# 5-Brake_Temp_Sensors.net
KiCad netlist of a schematic drawn in Altium Designer
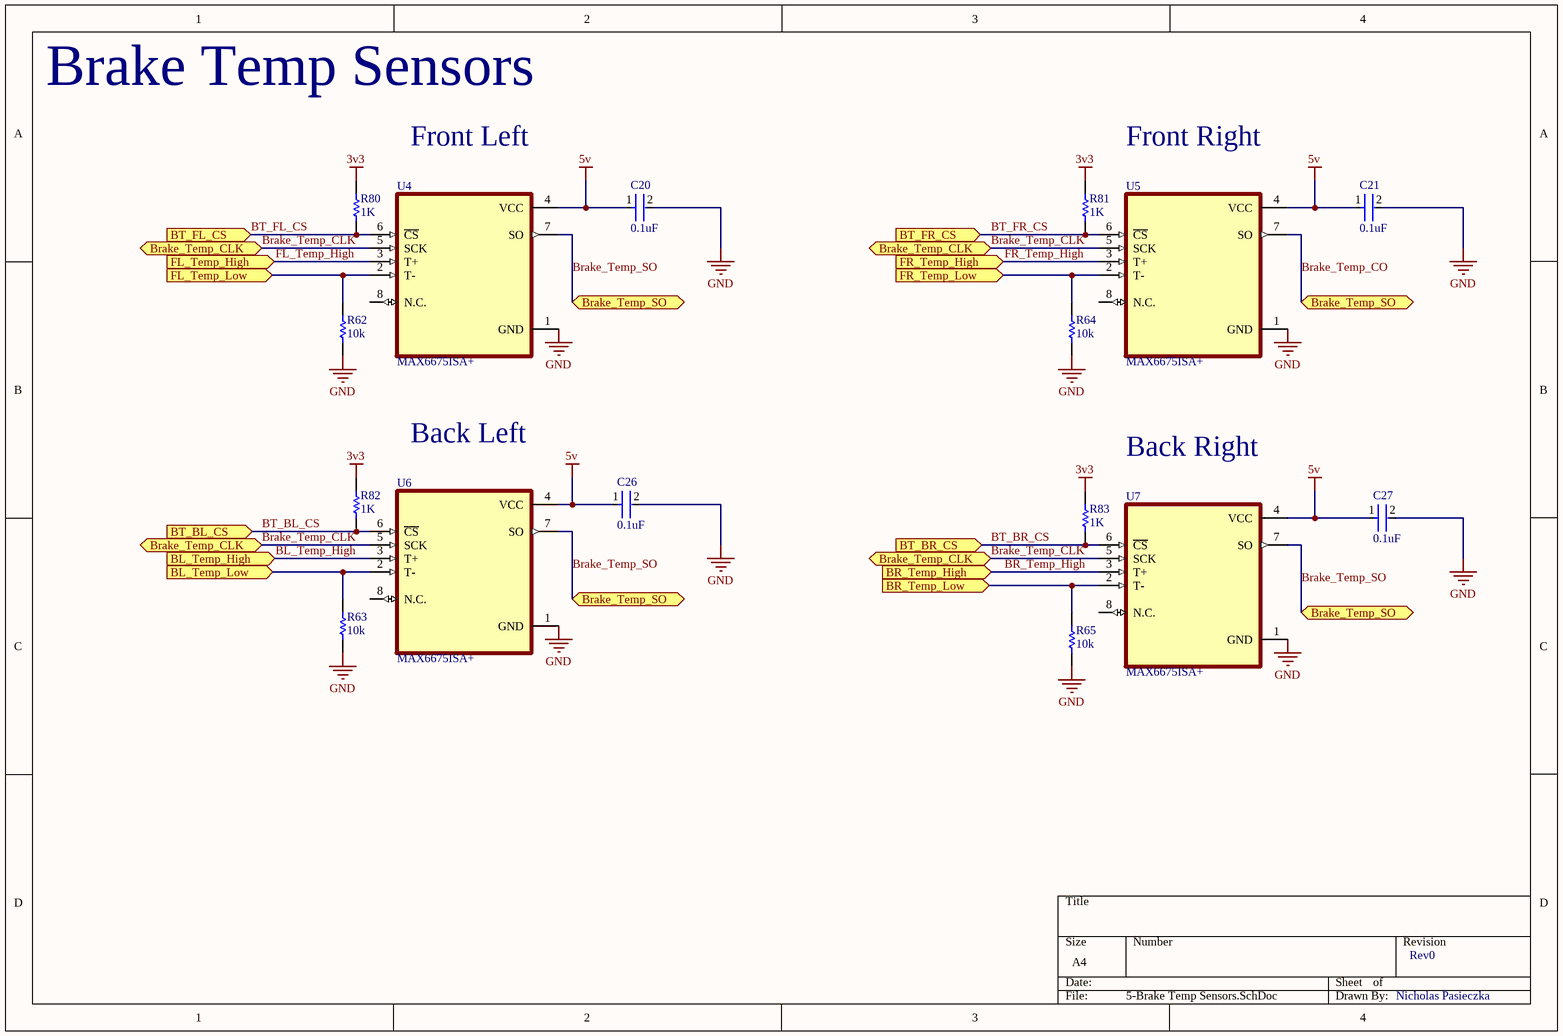
[diagram p0: 5-Brake Temp Sensors.SchDoc]

(export (version "E")
  (design (tool "Eeschema 10.0.6"))
  (components
    (comp (ref "C20")
      (value "0.1uF")
      (footprint "FP-CL17-IPC_C")
      (description "Cap Ceramic 100nF 10V X7R ±10% SMD 0402 +125°C Paper T/R")
      (fields (field (name "TOLERANCE") "10%"))
      (libsource (lib "Altium Content Vault") (part "b4654b650e69147ec39a6b967a45e02"))
    )
    (comp (ref "C21")
      (value "0.1uF")
      (footprint "FP-CL17-IPC_C")
      (description "Cap Ceramic 100nF 10V X7R ±10% SMD 0402 +125°C Paper T/R")
      (fields (field (name "TOLERANCE") "10%"))
      (libsource (lib "Altium Content Vault") (part "b4654b650e69147ec39a6b967a45e02"))
    )
    (comp (ref "C26")
      (value "0.1uF")
      (footprint "FP-CL17-IPC_C")
      (description "Cap Ceramic 100nF 10V X7R ±10% SMD 0402 +125°C Paper T/R")
      (fields (field (name "TOLERANCE") "10%"))
      (libsource (lib "Altium Content Vault") (part "b4654b650e69147ec39a6b967a45e02"))
    )
    (comp (ref "C27")
      (value "0.1uF")
      (footprint "FP-CL17-IPC_C")
      (description "Cap Ceramic 100nF 10V X7R ±10% SMD 0402 +125°C Paper T/R")
      (fields (field (name "TOLERANCE") "10%"))
      (libsource (lib "Altium Content Vault") (part "b4654b650e69147ec39a6b967a45e02"))
    )
    (comp (ref "R62")
      (value "10k")
      (footprint "1608[0603]")
      (description "Resistor")
      (fields
        (field (name "MANUFACTURER") "Yageo")
        (field (name "MANUFACTURER PART NUMBER") "RC0603JR-0710KL")
      )
      (libsource (lib "Miscellaneous Devices") (part "Res1"))
    )
    (comp (ref "R63")
      (value "10k")
      (footprint "1608[0603]")
      (description "Resistor")
      (fields
        (field (name "MANUFACTURER") "Yageo")
        (field (name "MANUFACTURER PART NUMBER") "RC0603JR-0710KL")
      )
      (libsource (lib "Miscellaneous Devices") (part "Res1"))
    )
    (comp (ref "R64")
      (value "10k")
      (footprint "1608[0603]")
      (description "Resistor")
      (fields
        (field (name "MANUFACTURER") "Yageo")
        (field (name "MANUFACTURER PART NUMBER") "RC0603JR-0710KL")
      )
      (libsource (lib "Miscellaneous Devices") (part "Res1"))
    )
    (comp (ref "R65")
      (value "10k")
      (footprint "1608[0603]")
      (description "Resistor")
      (fields
        (field (name "MANUFACTURER") "Yageo")
        (field (name "MANUFACTURER PART NUMBER") "RC0603JR-0710KL")
      )
      (libsource (lib "Miscellaneous Devices") (part "Res1"))
    )
    (comp (ref "R80")
      (value "1K")
      (footprint "1608[0603]")
      (description "Resistor")
      (fields (field (name "Comment") "Res1") (field (name "PUBLISHER") "Altium Limited"))
      (libsource (lib "Miscellaneous Devices") (part "Res1"))
    )
    (comp (ref "R81")
      (value "1K")
      (footprint "1608[0603]")
      (description "Resistor")
      (fields (field (name "Comment") "Res1") (field (name "PUBLISHER") "Altium Limited"))
      (libsource (lib "Miscellaneous Devices") (part "Res1"))
    )
    (comp (ref "R82")
      (value "1K")
      (footprint "1608[0603]")
      (description "Resistor")
      (fields (field (name "Comment") "Res1") (field (name "PUBLISHER") "Altium Limited"))
      (libsource (lib "Miscellaneous Devices") (part "Res1"))
    )
    (comp (ref "R83")
      (value "1K")
      (footprint "1608[0603]")
      (description "Resistor")
      (fields (field (name "Comment") "Res1") (field (name "PUBLISHER") "Altium Limited"))
      (libsource (lib "Miscellaneous Devices") (part "Res1"))
    )
    (comp (ref "U4")
      (value "MAX6675ISA+")
      (footprint "SOIC127P600X175-8N")
      (description "IC THERMOCOUP TO DGTL 8-SOIC")
      (fields (field (name "MF") "Maxim Integrated"))
      (libsource (lib "MAX6675ISA_") (part "MAX6675ISA+"))
    )
    (comp (ref "U5")
      (value "MAX6675ISA+")
      (footprint "SOIC127P600X175-8N")
      (description "IC THERMOCOUP TO DGTL 8-SOIC")
      (fields (field (name "MF") "Maxim Integrated"))
      (libsource (lib "MAX6675ISA_") (part "MAX6675ISA+"))
    )
    (comp (ref "U6")
      (value "MAX6675ISA+")
      (footprint "SOIC127P600X175-8N")
      (description "IC THERMOCOUP TO DGTL 8-SOIC")
      (fields (field (name "MF") "Maxim Integrated"))
      (libsource (lib "MAX6675ISA_") (part "MAX6675ISA+"))
    )
    (comp (ref "U7")
      (value "MAX6675ISA+")
      (footprint "SOIC127P600X175-8N")
      (description "IC THERMOCOUP TO DGTL 8-SOIC")
      (fields (field (name "MF") "Maxim Integrated"))
      (libsource (lib "MAX6675ISA_") (part "MAX6675ISA+"))
    )
  )
  (nets
    (net (code "1") (name "/BL_Temp_High") (class "Default")
      (node (ref "U6") (pin "3") (pinfunction "T+_3") (pintype "input"))
    )
    (net (code "2") (name "/BL_Temp_Low") (class "Default")
      (node (ref "R63") (pin "2") (pinfunction "2_2") (pintype "passive"))
      (node (ref "U6") (pin "2") (pinfunction "T-_2") (pintype "input"))
    )
    (net (code "3") (name "/BR_Temp_High") (class "Default")
      (node (ref "U7") (pin "3") (pinfunction "T+_3") (pintype "input"))
    )
    (net (code "4") (name "/BR_Temp_Low") (class "Default")
      (node (ref "R65") (pin "2") (pinfunction "2_2") (pintype "passive"))
      (node (ref "U7") (pin "2") (pinfunction "T-_2") (pintype "input"))
    )
    (net (code "5") (name "/BT_BL_CS") (class "Default")
      (node (ref "R82") (pin "1") (pinfunction "1_1") (pintype "passive"))
      (node (ref "U6") (pin "6") (pinfunction "~{CS}_6") (pintype "input"))
    )
    (net (code "6") (name "/BT_BR_CS") (class "Default")
      (node (ref "R83") (pin "1") (pinfunction "1_1") (pintype "passive"))
      (node (ref "U7") (pin "6") (pinfunction "~{CS}_6") (pintype "input"))
    )
    (net (code "7") (name "/BT_FL_CS") (class "Default")
      (node (ref "R80") (pin "1") (pinfunction "1_1") (pintype "passive"))
      (node (ref "U4") (pin "6") (pinfunction "~{CS}_6") (pintype "input"))
    )
    (net (code "8") (name "/BT_FR_CS") (class "Default")
      (node (ref "R81") (pin "1") (pinfunction "1_1") (pintype "passive"))
      (node (ref "U5") (pin "6") (pinfunction "~{CS}_6") (pintype "input"))
    )
    (net (code "9") (name "/Brake_Temp_CLK") (class "Default")
      (node (ref "U4") (pin "5") (pinfunction "SCK_5") (pintype "input"))
      (node (ref "U5") (pin "5") (pinfunction "SCK_5") (pintype "input"))
      (node (ref "U6") (pin "5") (pinfunction "SCK_5") (pintype "input"))
      (node (ref "U7") (pin "5") (pinfunction "SCK_5") (pintype "input"))
    )
    (net (code "10") (name "/Brake_Temp_CO") (class "Default")
      (node (ref "U4") (pin "7") (pinfunction "SO_7") (pintype "output"))
      (node (ref "U5") (pin "7") (pinfunction "SO_7") (pintype "output"))
      (node (ref "U6") (pin "7") (pinfunction "SO_7") (pintype "output"))
      (node (ref "U7") (pin "7") (pinfunction "SO_7") (pintype "output"))
    )
    (net (code "11") (name "/FL_Temp_High") (class "Default")
      (node (ref "U4") (pin "3") (pinfunction "T+_3") (pintype "input"))
    )
    (net (code "12") (name "/FL_Temp_Low") (class "Default")
      (node (ref "R62") (pin "2") (pinfunction "2_2") (pintype "passive"))
      (node (ref "U4") (pin "2") (pinfunction "T-_2") (pintype "input"))
    )
    (net (code "13") (name "/FR_Temp_High") (class "Default")
      (node (ref "U5") (pin "3") (pinfunction "T+_3") (pintype "input"))
    )
    (net (code "14") (name "/FR_Temp_Low") (class "Default")
      (node (ref "R64") (pin "2") (pinfunction "2_2") (pintype "passive"))
      (node (ref "U5") (pin "2") (pinfunction "T-_2") (pintype "input"))
    )
    (net (code "15") (name "3v3") (class "Default")
      (node (ref "R80") (pin "2") (pinfunction "2_2") (pintype "passive"))
      (node (ref "R81") (pin "2") (pinfunction "2_2") (pintype "passive"))
      (node (ref "R82") (pin "2") (pinfunction "2_2") (pintype "passive"))
      (node (ref "R83") (pin "2") (pinfunction "2_2") (pintype "passive"))
    )
    (net (code "16") (name "5v") (class "Default")
      (node (ref "C20") (pin "1") (pinfunction "1_1") (pintype "passive"))
      (node (ref "C21") (pin "1") (pinfunction "1_1") (pintype "passive"))
      (node (ref "C26") (pin "1") (pinfunction "1_1") (pintype "passive"))
      (node (ref "C27") (pin "1") (pinfunction "1_1") (pintype "passive"))
      (node (ref "U4") (pin "4") (pinfunction "VCC_4") (pintype "power_in"))
      (node (ref "U5") (pin "4") (pinfunction "VCC_4") (pintype "power_in"))
      (node (ref "U6") (pin "4") (pinfunction "VCC_4") (pintype "power_in"))
      (node (ref "U7") (pin "4") (pinfunction "VCC_4") (pintype "power_in"))
    )
    (net (code "17") (name "GND") (class "Default")
      (node (ref "C20") (pin "2") (pinfunction "2_2") (pintype "passive"))
      (node (ref "C21") (pin "2") (pinfunction "2_2") (pintype "passive"))
      (node (ref "C26") (pin "2") (pinfunction "2_2") (pintype "passive"))
      (node (ref "C27") (pin "2") (pinfunction "2_2") (pintype "passive"))
      (node (ref "R62") (pin "1") (pinfunction "1_1") (pintype "passive"))
      (node (ref "R63") (pin "1") (pinfunction "1_1") (pintype "passive"))
      (node (ref "R64") (pin "1") (pinfunction "1_1") (pintype "passive"))
      (node (ref "R65") (pin "1") (pinfunction "1_1") (pintype "passive"))
      (node (ref "U4") (pin "1") (pinfunction "GND_1") (pintype "power_in"))
      (node (ref "U5") (pin "1") (pinfunction "GND_1") (pintype "power_in"))
      (node (ref "U6") (pin "1") (pinfunction "GND_1") (pintype "power_in"))
      (node (ref "U7") (pin "1") (pinfunction "GND_1") (pintype "power_in"))
    )
    (net (code "18") (name "unconnected-(U4-N.C.-Pad8)") (class "Default")
      (node (ref "U4") (pin "8") (pinfunction "N.C._8") (pintype "bidirectional"))
    )
    (net (code "19") (name "unconnected-(U5-N.C.-Pad8)") (class "Default")
      (node (ref "U5") (pin "8") (pinfunction "N.C._8") (pintype "bidirectional"))
    )
    (net (code "20") (name "unconnected-(U6-N.C.-Pad8)") (class "Default")
      (node (ref "U6") (pin "8") (pinfunction "N.C._8") (pintype "bidirectional"))
    )
    (net (code "21") (name "unconnected-(U7-N.C.-Pad8)") (class "Default")
      (node (ref "U7") (pin "8") (pinfunction "N.C._8") (pintype "bidirectional"))
    )
  )
)
